# control_board.net
KiCad netlist of a schematic drawn in EAGLE
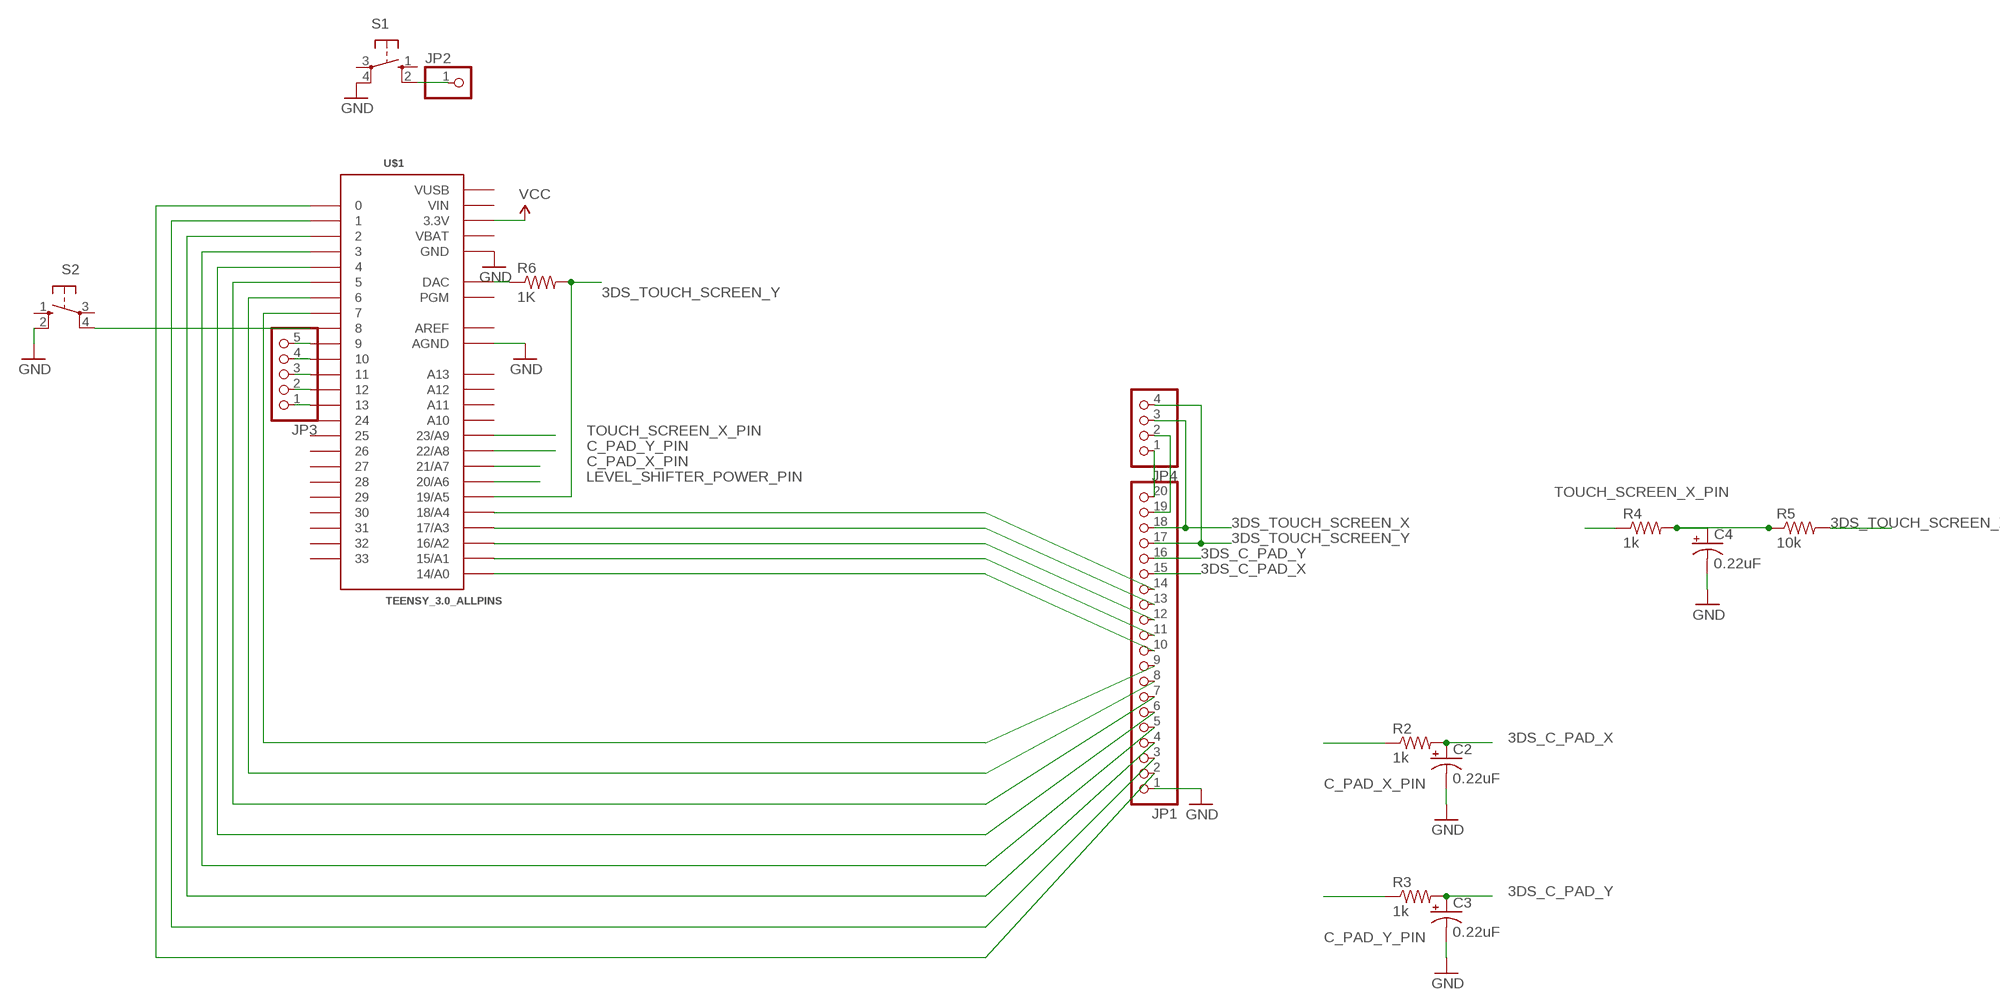
[diagram p0: schematic, sheet 1]

(export (version "E")
  (design (tool "Eeschema 10.0.6"))
  (components
    (comp (ref "C2")
      (value "0.22uF")
      (footprint "eagle-import:CPOL-RADIAL-10UF-25V")
      (libsource (lib "eagle-import") (part "10UF-25V-20%(PTH)"))
    )
    (comp (ref "C3")
      (value "0.22uF")
      (footprint "eagle-import:CPOL-RADIAL-10UF-25V")
      (libsource (lib "eagle-import") (part "10UF-25V-20%(PTH)"))
    )
    (comp (ref "C4")
      (value "0.22uF")
      (footprint "eagle-import:CPOL-RADIAL-10UF-25V")
      (libsource (lib "eagle-import") (part "10UF-25V-20%(PTH)"))
    )
    (comp (ref "JP1")
      (value "PINHD-1X20")
      (footprint "eagle-import:1X20")
      (libsource (lib "eagle-import") (part "PINHD-1X20"))
    )
    (comp (ref "JP2")
      (value "PINHD-1X1")
      (footprint "eagle-import:1X01")
      (libsource (lib "eagle-import") (part "PINHD-1X1"))
    )
    (comp (ref "JP3")
      (value "PINHD-1X5")
      (footprint "eagle-import:1X05")
      (libsource (lib "eagle-import") (part "PINHD-1X5"))
    )
    (comp (ref "JP4")
      (value "PINHD-1X4")
      (footprint "eagle-import:1X04")
      (libsource (lib "eagle-import") (part "PINHD-1X4"))
    )
    (comp (ref "R2")
      (value "1k")
      (footprint "eagle-import:0207_7")
      (libsource (lib "eagle-import") (part "resistor_R-US_0207/7"))
    )
    (comp (ref "R3")
      (value "1k")
      (footprint "eagle-import:0207_7")
      (libsource (lib "eagle-import") (part "resistor_R-US_0207/7"))
    )
    (comp (ref "R4")
      (value "1k")
      (footprint "eagle-import:0207_7")
      (libsource (lib "eagle-import") (part "resistor_R-US_0207/7"))
    )
    (comp (ref "R5")
      (value "10k")
      (footprint "eagle-import:AXIAL-0.1")
      (libsource (lib "eagle-import") (part "RESISTORPTH-1/4W-VERT"))
    )
    (comp (ref "R6")
      (value "1K")
      (footprint "eagle-import:0207_7")
      (libsource (lib "eagle-import") (part "R-US_0207/7"))
    )
    (comp (ref "S1")
      (value "10-XX")
      (footprint "eagle-import:B3F-10XX")
      (fields (field (name "MPN") "B3F-1000"))
      (libsource (lib "eagle-import") (part "10-XX"))
    )
    (comp (ref "S2")
      (value "10-XX")
      (footprint "eagle-import:B3F-10XX")
      (fields (field (name "MPN") "B3F-1000"))
      (libsource (lib "eagle-import") (part "10-XX"))
    )
    (comp (ref "U$1")
      (value "TEENSY_3.0_ALLPINS")
      (footprint "eagle-import:TEENSY_3.0_ALLPINS")
      (libsource (lib "eagle-import") (part "TEENSY_3.0_ALLPINS"))
    )
  )
  (nets
    (net (code "1") (name "/3DS_C_PAD_X") (class "Default")
      (node (ref "C2") (pin "1") (pinfunction "+_1") (pintype "passive"))
      (node (ref "JP1") (pin "15") (pinfunction "15_15") (pintype "passive"))
      (node (ref "R2") (pin "2") (pinfunction "2_2") (pintype "passive"))
    )
    (net (code "2") (name "/3DS_C_PAD_Y") (class "Default")
      (node (ref "C3") (pin "1") (pinfunction "+_1") (pintype "passive"))
      (node (ref "JP1") (pin "16") (pinfunction "16_16") (pintype "passive"))
      (node (ref "R3") (pin "2") (pinfunction "2_2") (pintype "passive"))
    )
    (net (code "3") (name "/3DS_TOUCH_SCREEN_X") (class "Default")
      (node (ref "JP1") (pin "18") (pinfunction "18_18") (pintype "passive"))
      (node (ref "JP4") (pin "3") (pinfunction "3_3") (pintype "passive"))
      (node (ref "R5") (pin "P$2") (pinfunction "2_P$2") (pintype "passive"))
    )
    (net (code "4") (name "/3DS_TOUCH_SCREEN_Y") (class "Default")
      (node (ref "JP1") (pin "17") (pinfunction "17_17") (pintype "passive"))
      (node (ref "JP4") (pin "4") (pinfunction "4_4") (pintype "passive"))
      (node (ref "R6") (pin "2") (pinfunction "2_2") (pintype "passive"))
      (node (ref "U$1") (pin "19/A5") (pinfunction "19/A5_19/A5") (pintype "bidirectional"))
    )
    (net (code "5") (name "/AREF") (class "Default")
      (node (ref "U$1") (pin "AREF") (pinfunction "AREF_AREF") (pintype "power_in"))
    )
    (net (code "6") (name "/C_PAD_X_PIN") (class "Default")
      (node (ref "R2") (pin "1") (pinfunction "1_1") (pintype "passive"))
      (node (ref "U$1") (pin "21/A7") (pinfunction "21/A7_21/A7") (pintype "bidirectional"))
    )
    (net (code "7") (name "/C_PAD_Y_PIN") (class "Default")
      (node (ref "R3") (pin "1") (pinfunction "1_1") (pintype "passive"))
      (node (ref "U$1") (pin "22/A8") (pinfunction "22/A8_22/A8") (pintype "bidirectional"))
    )
    (net (code "8") (name "/LEVEL_SHIFTER_POWER_PIN") (class "Default")
      (node (ref "U$1") (pin "20/A6") (pinfunction "20/A6_20/A6") (pintype "bidirectional"))
    )
    (net (code "9") (name "/TOUCH_SCREEN_X_PIN") (class "Default")
      (node (ref "R4") (pin "1") (pinfunction "1_1") (pintype "passive"))
      (node (ref "U$1") (pin "23/A9") (pinfunction "23/A9_23/A9") (pintype "bidirectional"))
    )
    (net (code "10") (name "/VBAT") (class "Default")
      (node (ref "U$1") (pin "VBAT") (pinfunction "VBAT_VBAT") (pintype "power_in"))
    )
    (net (code "11") (name "/VIN") (class "Default")
      (node (ref "U$1") (pin "VIN") (pinfunction "VIN_VIN") (pintype "power_in"))
    )
    (net (code "12") (name "/VUSB") (class "Default")
      (node (ref "U$1") (pin "VUSB") (pinfunction "VUSB_VUSB") (pintype "power_in"))
    )
    (net (code "13") (name "GND") (class "Default")
      (node (ref "C2") (pin "2") (pinfunction "-_2") (pintype "passive"))
      (node (ref "C3") (pin "2") (pinfunction "-_2") (pintype "passive"))
      (node (ref "C4") (pin "2") (pinfunction "-_2") (pintype "passive"))
      (node (ref "JP1") (pin "1") (pinfunction "1_1") (pintype "passive"))
      (node (ref "S1") (pin "4") (pinfunction "P1_4") (pintype "passive"))
      (node (ref "S2") (pin "2") (pinfunction "S1_2") (pintype "passive"))
      (node (ref "U$1") (pin "AGND") (pinfunction "AGND_AGND") (pintype "power_in"))
      (node (ref "U$1") (pin "GND") (pinfunction "GND_GND") (pintype "power_in"))
      (node (ref "U$1") (pin "GND1") (pinfunction "GND_GND1") (pintype "power_in"))
      (node (ref "U$1") (pin "GND2") (pinfunction "GND_GND2") (pintype "power_in"))
    )
    (net (code "14") (name "Net-(C4-+)") (class "Default")
      (node (ref "C4") (pin "1") (pinfunction "+_1") (pintype "passive"))
      (node (ref "R4") (pin "2") (pinfunction "2_2") (pintype "passive"))
      (node (ref "R5") (pin "P$1") (pinfunction "1_P$1") (pintype "passive"))
    )
    (net (code "15") (name "Net-(JP1-Pad2)") (class "Default")
      (node (ref "JP1") (pin "2") (pinfunction "2_2") (pintype "passive"))
      (node (ref "U$1") (pin "0") (pinfunction "0_0") (pintype "bidirectional"))
    )
    (net (code "16") (name "Net-(JP1-Pad3)") (class "Default")
      (node (ref "JP1") (pin "3") (pinfunction "3_3") (pintype "passive"))
      (node (ref "U$1") (pin "1") (pinfunction "1_1") (pintype "bidirectional"))
    )
    (net (code "17") (name "Net-(JP1-Pad4)") (class "Default")
      (node (ref "JP1") (pin "4") (pinfunction "4_4") (pintype "passive"))
      (node (ref "U$1") (pin "2") (pinfunction "2_2") (pintype "bidirectional"))
    )
    (net (code "18") (name "Net-(JP1-Pad5)") (class "Default")
      (node (ref "JP1") (pin "5") (pinfunction "5_5") (pintype "passive"))
      (node (ref "U$1") (pin "3") (pinfunction "3_3") (pintype "bidirectional"))
    )
    (net (code "19") (name "Net-(JP1-Pad6)") (class "Default")
      (node (ref "JP1") (pin "6") (pinfunction "6_6") (pintype "passive"))
      (node (ref "U$1") (pin "4") (pinfunction "4_4") (pintype "bidirectional"))
    )
    (net (code "20") (name "Net-(JP1-Pad7)") (class "Default")
      (node (ref "JP1") (pin "7") (pinfunction "7_7") (pintype "passive"))
      (node (ref "U$1") (pin "5") (pinfunction "5_5") (pintype "bidirectional"))
    )
    (net (code "21") (name "Net-(JP1-Pad8)") (class "Default")
      (node (ref "JP1") (pin "8") (pinfunction "8_8") (pintype "passive"))
      (node (ref "U$1") (pin "6") (pinfunction "6_6") (pintype "bidirectional"))
    )
    (net (code "22") (name "Net-(JP1-Pad9)") (class "Default")
      (node (ref "JP1") (pin "9") (pinfunction "9_9") (pintype "passive"))
      (node (ref "U$1") (pin "7") (pinfunction "7_7") (pintype "bidirectional"))
    )
    (net (code "23") (name "Net-(JP1-Pad10)") (class "Default")
      (node (ref "JP1") (pin "10") (pinfunction "10_10") (pintype "passive"))
      (node (ref "U$1") (pin "14/A0") (pinfunction "14/A0_14/A0") (pintype "bidirectional"))
    )
    (net (code "24") (name "Net-(JP1-Pad11)") (class "Default")
      (node (ref "JP1") (pin "11") (pinfunction "11_11") (pintype "passive"))
      (node (ref "U$1") (pin "15/A1") (pinfunction "15/A1_15/A1") (pintype "bidirectional"))
    )
    (net (code "25") (name "Net-(JP1-Pad12)") (class "Default")
      (node (ref "JP1") (pin "12") (pinfunction "12_12") (pintype "passive"))
      (node (ref "U$1") (pin "16/A2") (pinfunction "16/A2_16/A2") (pintype "bidirectional"))
    )
    (net (code "26") (name "Net-(JP1-Pad13)") (class "Default")
      (node (ref "JP1") (pin "13") (pinfunction "13_13") (pintype "passive"))
      (node (ref "U$1") (pin "17/A3") (pinfunction "17/A3_17/A3") (pintype "bidirectional"))
    )
    (net (code "27") (name "Net-(JP1-Pad14)") (class "Default")
      (node (ref "JP1") (pin "14") (pinfunction "14_14") (pintype "passive"))
      (node (ref "U$1") (pin "18/A4") (pinfunction "18/A4_18/A4") (pintype "bidirectional"))
    )
    (net (code "28") (name "Net-(JP1-Pad19)") (class "Default")
      (node (ref "JP1") (pin "19") (pinfunction "19_19") (pintype "passive"))
      (node (ref "JP4") (pin "2") (pinfunction "2_2") (pintype "passive"))
    )
    (net (code "29") (name "Net-(JP1-Pad20)") (class "Default")
      (node (ref "JP1") (pin "20") (pinfunction "20_20") (pintype "passive"))
      (node (ref "JP4") (pin "1") (pinfunction "1_1") (pintype "passive"))
    )
    (net (code "30") (name "Net-(JP3-Pad1)") (class "Default")
      (node (ref "JP3") (pin "1") (pinfunction "1_1") (pintype "passive"))
      (node (ref "U$1") (pin "13") (pinfunction "13_13") (pintype "bidirectional"))
    )
    (net (code "31") (name "Net-(JP3-Pad2)") (class "Default")
      (node (ref "JP3") (pin "2") (pinfunction "2_2") (pintype "passive"))
      (node (ref "U$1") (pin "12") (pinfunction "12_12") (pintype "bidirectional"))
    )
    (net (code "32") (name "Net-(JP3-Pad3)") (class "Default")
      (node (ref "JP3") (pin "3") (pinfunction "3_3") (pintype "passive"))
      (node (ref "U$1") (pin "11") (pinfunction "11_11") (pintype "bidirectional"))
    )
    (net (code "33") (name "Net-(JP3-Pad4)") (class "Default")
      (node (ref "JP3") (pin "4") (pinfunction "4_4") (pintype "passive"))
      (node (ref "U$1") (pin "10") (pinfunction "10_10") (pintype "bidirectional"))
    )
    (net (code "34") (name "Net-(JP3-Pad5)") (class "Default")
      (node (ref "JP3") (pin "5") (pinfunction "5_5") (pintype "passive"))
      (node (ref "U$1") (pin "9") (pinfunction "9_9") (pintype "bidirectional"))
    )
    (net (code "35") (name "Net-(S1-S1)") (class "Default")
      (node (ref "JP2") (pin "1") (pinfunction "1_1") (pintype "passive"))
      (node (ref "S1") (pin "2") (pinfunction "S1_2") (pintype "passive"))
    )
    (net (code "36") (name "Net-(S2-P1)") (class "Default")
      (node (ref "S2") (pin "4") (pinfunction "P1_4") (pintype "passive"))
      (node (ref "U$1") (pin "8") (pinfunction "8_8") (pintype "bidirectional"))
    )
    (net (code "37") (name "Net-(U$1-DAC)") (class "Default")
      (node (ref "R6") (pin "1") (pinfunction "1_1") (pintype "passive"))
      (node (ref "U$1") (pin "RESET") (pinfunction "DAC_RESET") (pintype "bidirectional"))
    )
    (net (code "38") (name "VCC") (class "Default")
      (node (ref "U$1") (pin "3.3V") (pinfunction "3.3V_3.3V") (pintype "power_in"))
      (node (ref "U$1") (pin "3.3V1") (pinfunction "3.3V_3.3V1") (pintype "power_in"))
      (node (ref "U$1") (pin "3.3V2") (pinfunction "3.3V_3.3V2") (pintype "power_in"))
    )
    (net (code "39") (name "unconnected-(S1-P-Pad3)") (class "Default")
      (node (ref "S1") (pin "3") (pinfunction "P_3") (pintype "passive"))
    )
    (net (code "40") (name "unconnected-(S1-S-Pad1)") (class "Default")
      (node (ref "S1") (pin "1") (pinfunction "S_1") (pintype "passive"))
    )
    (net (code "41") (name "unconnected-(S2-P-Pad3)") (class "Default")
      (node (ref "S2") (pin "3") (pinfunction "P_3") (pintype "passive"))
    )
    (net (code "42") (name "unconnected-(S2-S-Pad1)") (class "Default")
      (node (ref "S2") (pin "1") (pinfunction "S_1") (pintype "passive"))
    )
    (net (code "43") (name "unconnected-(U$1-Pad24)") (class "Default")
      (node (ref "U$1") (pin "24") (pinfunction "24_24") (pintype "bidirectional"))
    )
    (net (code "44") (name "unconnected-(U$1-Pad25)") (class "Default")
      (node (ref "U$1") (pin "25") (pinfunction "25_25") (pintype "bidirectional"))
    )
    (net (code "45") (name "unconnected-(U$1-Pad26)") (class "Default")
      (node (ref "U$1") (pin "26") (pinfunction "26_26") (pintype "bidirectional"))
    )
    (net (code "46") (name "unconnected-(U$1-Pad27)") (class "Default")
      (node (ref "U$1") (pin "27") (pinfunction "27_27") (pintype "bidirectional"))
    )
    (net (code "47") (name "unconnected-(U$1-Pad28)") (class "Default")
      (node (ref "U$1") (pin "28") (pinfunction "28_28") (pintype "bidirectional"))
    )
    (net (code "48") (name "unconnected-(U$1-Pad29)") (class "Default")
      (node (ref "U$1") (pin "29") (pinfunction "29_29") (pintype "bidirectional"))
    )
    (net (code "49") (name "unconnected-(U$1-Pad30)") (class "Default")
      (node (ref "U$1") (pin "30") (pinfunction "30_30") (pintype "bidirectional"))
    )
    (net (code "50") (name "unconnected-(U$1-Pad31)") (class "Default")
      (node (ref "U$1") (pin "31") (pinfunction "31_31") (pintype "bidirectional"))
    )
    (net (code "51") (name "unconnected-(U$1-Pad32)") (class "Default")
      (node (ref "U$1") (pin "32") (pinfunction "32_32") (pintype "bidirectional"))
    )
    (net (code "52") (name "unconnected-(U$1-Pad33)") (class "Default")
      (node (ref "U$1") (pin "33") (pinfunction "33_33") (pintype "bidirectional"))
    )
    (net (code "53") (name "unconnected-(U$1-PadA10)") (class "Default")
      (node (ref "U$1") (pin "A10") (pinfunction "A10_A10") (pintype "bidirectional"))
    )
    (net (code "54") (name "unconnected-(U$1-PadA11)") (class "Default")
      (node (ref "U$1") (pin "A11") (pinfunction "A11_A11") (pintype "bidirectional"))
    )
    (net (code "55") (name "unconnected-(U$1-PadA12)") (class "Default")
      (node (ref "U$1") (pin "A12") (pinfunction "A12_A12") (pintype "bidirectional"))
    )
    (net (code "56") (name "unconnected-(U$1-PadA13)") (class "Default")
      (node (ref "U$1") (pin "A13") (pinfunction "A13_A13") (pintype "bidirectional"))
    )
    (net (code "57") (name "unconnected-(U$1-PadPGM)") (class "Default")
      (node (ref "U$1") (pin "PGM") (pinfunction "PGM_PGM") (pintype "bidirectional"))
    )
  )
)
